# main_miniusb.net
KiCad netlist of a schematic drawn in Altium Designer
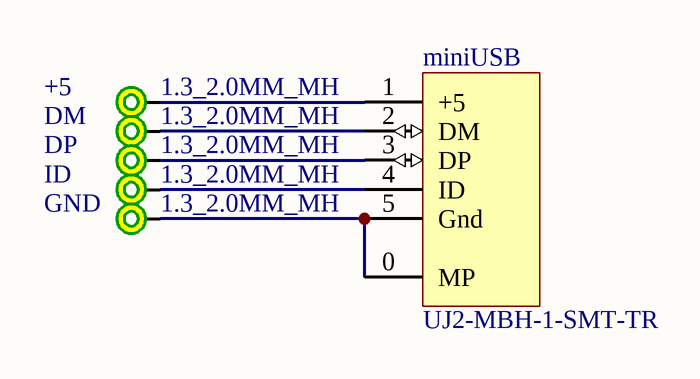
[diagram p0: main_miniusb.SchDoc]

(export (version "E")
  (design (tool "Eeschema 10.0.6"))
  (components
    (comp (ref "+5")
      (value "1.3_2.0MM_MH")
      (footprint "1.3_2.0MM_PH")
      (fields
        (field (name "PART NUMBER") "PCB_0092")
        (field (name "MANUFACTURER") "Misc PCB")
        (field (name "MANUFACTURER PART NUMBER") "S46")
        (field (name "PUBLISHER") "shawn@shaolo.com")
        (field (name "REVIEWER") "shawn@shaolo.com")
      )
      (libsource (lib "Altium Access") (part "Plated Hole"))
    )
    (comp (ref "DM")
      (value "1.3_2.0MM_MH")
      (footprint "1.3_2.0MM_PH")
      (fields
        (field (name "PART NUMBER") "PCB_0092")
        (field (name "MANUFACTURER") "Misc PCB")
        (field (name "MANUFACTURER PART NUMBER") "S46")
        (field (name "PUBLISHER") "shawn@shaolo.com")
        (field (name "REVIEWER") "shawn@shaolo.com")
      )
      (libsource (lib "Altium Access") (part "Plated Hole"))
    )
    (comp (ref "DP")
      (value "1.3_2.0MM_MH")
      (footprint "1.3_2.0MM_PH")
      (fields
        (field (name "PART NUMBER") "PCB_0092")
        (field (name "MANUFACTURER") "Misc PCB")
        (field (name "MANUFACTURER PART NUMBER") "S46")
        (field (name "PUBLISHER") "shawn@shaolo.com")
        (field (name "REVIEWER") "shawn@shaolo.com")
      )
      (libsource (lib "Altium Access") (part "Plated Hole"))
    )
    (comp (ref "GND")
      (value "1.3_2.0MM_MH")
      (footprint "1.3_2.0MM_PH")
      (fields
        (field (name "PART NUMBER") "PCB_0092")
        (field (name "MANUFACTURER") "Misc PCB")
        (field (name "MANUFACTURER PART NUMBER") "S46")
        (field (name "PUBLISHER") "shawn@shaolo.com")
        (field (name "REVIEWER") "shawn@shaolo.com")
      )
      (libsource (lib "Altium Access") (part "Plated Hole"))
    )
    (comp (ref "ID")
      (value "1.3_2.0MM_MH")
      (footprint "1.3_2.0MM_PH")
      (fields
        (field (name "PART NUMBER") "PCB_0092")
        (field (name "MANUFACTURER") "Misc PCB")
        (field (name "MANUFACTURER PART NUMBER") "S46")
        (field (name "PUBLISHER") "shawn@shaolo.com")
        (field (name "REVIEWER") "shawn@shaolo.com")
      )
      (libsource (lib "Altium Access") (part "Plated Hole"))
    )
    (comp (ref "miniUSB")
      (value "UJ2-MBH-1-SMT-TR")
      (footprint "USB MINI B W PEGS - UJ2")
      (description "USB JACK 2.0, MINI B TYPE, 5 PIN")
      (fields
        (field (name "PART NUMBER") "CONN_0247")
        (field (name "MANUFACTURER") "Cui")
        (field (name "PUBLISHER") "shawn@shaolo.com")
        (field (name "REVIEWER") "shawn@shaolo.com")
      )
      (libsource (lib "Altium Access") (part "USB_MINI"))
    )
  )
  (nets
    (net (code "1") (name "Net-(miniUSB-+5)") (class "Default")
      (node (ref "+5") (pin "1") (pinfunction "1_1") (pintype "passive"))
      (node (ref "miniUSB") (pin "1") (pinfunction "+5_1") (pintype "power_in"))
    )
    (net (code "2") (name "Net-(miniUSB-DM)") (class "Default")
      (node (ref "DM") (pin "1") (pinfunction "1_1") (pintype "passive"))
      (node (ref "miniUSB") (pin "2") (pinfunction "DM_2") (pintype "bidirectional"))
    )
    (net (code "3") (name "Net-(miniUSB-DP)") (class "Default")
      (node (ref "DP") (pin "1") (pinfunction "1_1") (pintype "passive"))
      (node (ref "miniUSB") (pin "3") (pinfunction "DP_3") (pintype "bidirectional"))
    )
    (net (code "4") (name "Net-(miniUSB-Gnd)") (class "Default")
      (node (ref "GND") (pin "1") (pinfunction "1_1") (pintype "passive"))
      (node (ref "miniUSB") (pin "0") (pinfunction "MP_0") (pintype "passive"))
      (node (ref "miniUSB") (pin "5") (pinfunction "Gnd_5") (pintype "power_in"))
    )
    (net (code "5") (name "Net-(miniUSB-ID)") (class "Default")
      (node (ref "ID") (pin "1") (pinfunction "1_1") (pintype "passive"))
      (node (ref "miniUSB") (pin "4") (pinfunction "ID_4") (pintype "passive"))
    )
  )
)
